# FridgeWarninig_0_3.net
KiCad netlist of a schematic drawn in EAGLE
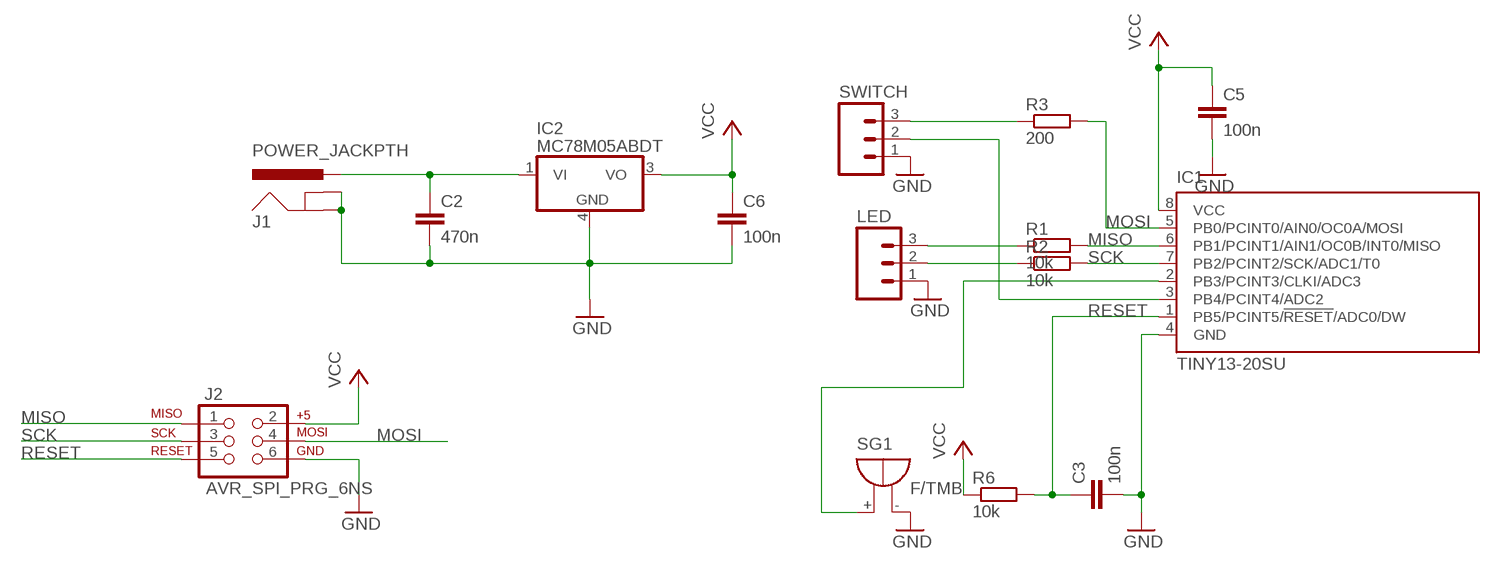
[diagram p0: schematic, sheet 1]

(export (version "E")
  (design (tool "Eeschema 10.0.6"))
  (components
    (comp (ref "C2")
      (value "470n")
      (footprint "eagle-import:C0603")
      (libsource (lib "eagle-import") (part "C-EUC0603"))
    )
    (comp (ref "C3")
      (value "100n")
      (footprint "eagle-import:C0603")
      (libsource (lib "eagle-import") (part "C-EUC0603"))
    )
    (comp (ref "C5")
      (value "100n")
      (footprint "eagle-import:C0603")
      (libsource (lib "eagle-import") (part "C-EUC0603"))
    )
    (comp (ref "C6")
      (value "100n")
      (footprint "eagle-import:C0603")
      (libsource (lib "eagle-import") (part "C-EUC0603"))
    )
    (comp (ref "IC1")
      (value "TINY13-20SU")
      (footprint "eagle-import:8S2")
      (fields (field (name "MPN") "ATTINY13-20SU"))
      (libsource (lib "eagle-import") (part "TINY13SU-20"))
    )
    (comp (ref "IC2")
      (value "MC78M05ABDT")
      (footprint "eagle-import:DPACK_3")
      (libsource (lib "eagle-import") (part "MC78M05ABDT"))
    )
    (comp (ref "J1")
      (value "POWER_JACKPTH")
      (footprint "eagle-import:POWER_JACK_PTH")
      (libsource (lib "eagle-import") (part "POWER_JACKPTH"))
    )
    (comp (ref "J2")
      (value "AVR_SPI_PRG_6NS")
      (footprint "eagle-import:2X3-NS")
      (libsource (lib "eagle-import") (part "AVR_SPI_PRG_6NS"))
    )
    (comp (ref "LED")
      (value "M03JST-PTH")
      (footprint "eagle-import:JST-3-PTH")
      (libsource (lib "eagle-import") (part "M03JST-PTH"))
    )
    (comp (ref "R1")
      (value "10k")
      (footprint "eagle-import:R0603")
      (libsource (lib "eagle-import") (part "R-EU_R0603"))
    )
    (comp (ref "R2")
      (value "10k")
      (footprint "eagle-import:R0603")
      (libsource (lib "eagle-import") (part "R-EU_R0603"))
    )
    (comp (ref "R3")
      (value "200")
      (footprint "eagle-import:R0603")
      (libsource (lib "eagle-import") (part "R-EU_R0603"))
    )
    (comp (ref "R6")
      (value "10k")
      (footprint "eagle-import:R0603")
      (libsource (lib "eagle-import") (part "R-EU_R0603"))
    )
    (comp (ref "SG1")
      (value "F/TMB")
      (footprint "eagle-import:F_TMB")
      (libsource (lib "eagle-import") (part "F/TMB"))
    )
    (comp (ref "SWITCH")
      (value "M03JST-PTH")
      (footprint "eagle-import:JST-3-PTH")
      (libsource (lib "eagle-import") (part "M03JST-PTH"))
    )
  )
  (nets
    (net (code "1") (name "/MISO") (class "Default")
      (node (ref "IC1") (pin "6") (pinfunction "PB1/PCINT1/AIN1/OC0B/INT0/MISO_6") (pintype "bidirectional"))
      (node (ref "J2") (pin "1") (pinfunction "1_1") (pintype "passive"))
      (node (ref "R1") (pin "2") (pinfunction "2_2") (pintype "passive"))
    )
    (net (code "2") (name "/MOSI") (class "Default")
      (node (ref "IC1") (pin "5") (pinfunction "PB0/PCINT0/AIN0/OC0A/MOSI_5") (pintype "bidirectional"))
      (node (ref "J2") (pin "4") (pinfunction "4_4") (pintype "passive"))
      (node (ref "R3") (pin "2") (pinfunction "2_2") (pintype "passive"))
    )
    (net (code "3") (name "/RESET") (class "Default")
      (node (ref "C3") (pin "1") (pinfunction "1_1") (pintype "passive"))
      (node (ref "IC1") (pin "1") (pinfunction "PB5/PCINT5/~{RESET}/ADC0/DW_1") (pintype "bidirectional"))
      (node (ref "J2") (pin "5") (pinfunction "5_5") (pintype "passive"))
      (node (ref "R6") (pin "2") (pinfunction "2_2") (pintype "passive"))
    )
    (net (code "4") (name "/SCK") (class "Default")
      (node (ref "IC1") (pin "7") (pinfunction "PB2/PCINT2/SCK/ADC1/T0_7") (pintype "bidirectional"))
      (node (ref "J2") (pin "3") (pinfunction "3_3") (pintype "passive"))
      (node (ref "R2") (pin "2") (pinfunction "2_2") (pintype "passive"))
    )
    (net (code "5") (name "GND") (class "Default")
      (node (ref "C2") (pin "2") (pinfunction "2_2") (pintype "passive"))
      (node (ref "C3") (pin "2") (pinfunction "2_2") (pintype "passive"))
      (node (ref "C5") (pin "2") (pinfunction "2_2") (pintype "passive"))
      (node (ref "C6") (pin "2") (pinfunction "2_2") (pintype "passive"))
      (node (ref "IC1") (pin "4") (pinfunction "GND_4") (pintype "power_in"))
      (node (ref "IC2") (pin "4") (pinfunction "GND_4") (pintype "passive"))
      (node (ref "J1") (pin "GND") (pinfunction "GND_GND") (pintype "bidirectional"))
      (node (ref "J1") (pin "GNDBREAK") (pinfunction "GNDBREAK_GNDBREAK") (pintype "bidirectional"))
      (node (ref "J2") (pin "6") (pinfunction "6_6") (pintype "passive"))
      (node (ref "LED") (pin "1") (pinfunction "1_1") (pintype "passive"))
      (node (ref "SG1") (pin "-") (pinfunction "-_-") (pintype "passive"))
      (node (ref "SWITCH") (pin "1") (pinfunction "1_1") (pintype "passive"))
    )
    (net (code "6") (name "Net-(IC1-PB3{slash}PCINT3{slash}CLKI{slash}ADC3)") (class "Default")
      (node (ref "IC1") (pin "2") (pinfunction "PB3/PCINT3/CLKI/ADC3_2") (pintype "bidirectional"))
      (node (ref "SG1") (pin "+") (pinfunction "+_+") (pintype "passive"))
    )
    (net (code "7") (name "Net-(IC1-PB4{slash}PCINT4{slash}ADC2)") (class "Default")
      (node (ref "IC1") (pin "3") (pinfunction "PB4/PCINT4/ADC2_3") (pintype "bidirectional"))
      (node (ref "SWITCH") (pin "2") (pinfunction "2_2") (pintype "passive"))
    )
    (net (code "8") (name "Net-(IC2-VI)") (class "Default")
      (node (ref "C2") (pin "1") (pinfunction "1_1") (pintype "passive"))
      (node (ref "IC2") (pin "1") (pinfunction "VI_1") (pintype "input"))
      (node (ref "J1") (pin "PWR") (pinfunction "PWR_PWR") (pintype "bidirectional"))
    )
    (net (code "9") (name "Net-(LED-Pad2)") (class "Default")
      (node (ref "LED") (pin "2") (pinfunction "2_2") (pintype "passive"))
      (node (ref "R2") (pin "1") (pinfunction "1_1") (pintype "passive"))
    )
    (net (code "10") (name "Net-(LED-Pad3)") (class "Default")
      (node (ref "LED") (pin "3") (pinfunction "3_3") (pintype "passive"))
      (node (ref "R1") (pin "1") (pinfunction "1_1") (pintype "passive"))
    )
    (net (code "11") (name "Net-(R3-Pad1)") (class "Default")
      (node (ref "R3") (pin "1") (pinfunction "1_1") (pintype "passive"))
      (node (ref "SWITCH") (pin "3") (pinfunction "3_3") (pintype "passive"))
    )
    (net (code "12") (name "VCC") (class "Default")
      (node (ref "C5") (pin "1") (pinfunction "1_1") (pintype "passive"))
      (node (ref "C6") (pin "1") (pinfunction "1_1") (pintype "passive"))
      (node (ref "IC1") (pin "8") (pinfunction "VCC_8") (pintype "power_in"))
      (node (ref "IC2") (pin "3") (pinfunction "VO_3") (pintype "passive"))
      (node (ref "J2") (pin "2") (pinfunction "2_2") (pintype "passive"))
      (node (ref "R6") (pin "1") (pinfunction "1_1") (pintype "passive"))
    )
  )
)
